# robot_vac.net
KiCad netlist of a schematic drawn in EAGLE
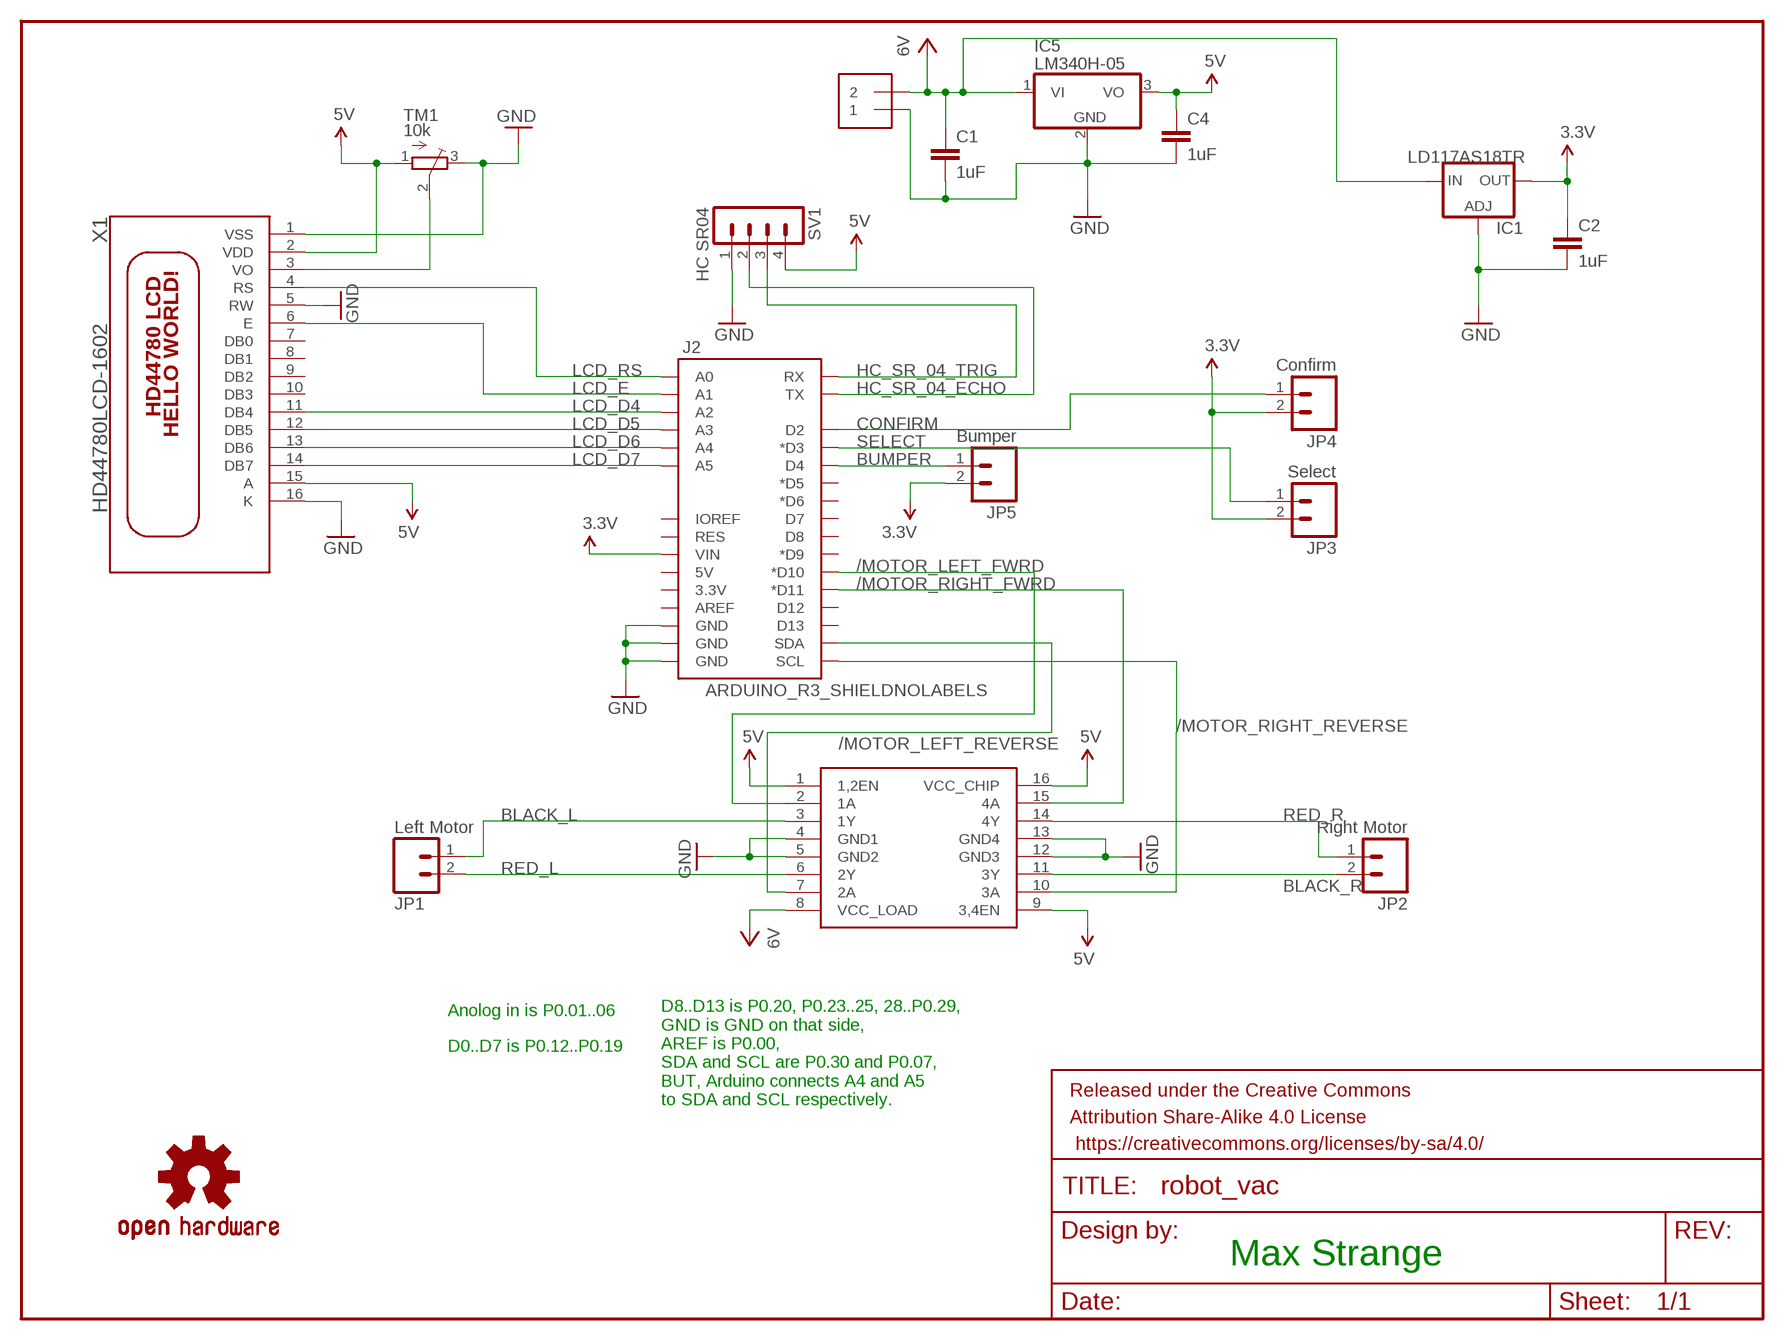
[diagram p0: schematic, sheet 1]

(export (version "E")
  (design (tool "Eeschema 10.0.6"))
  (components
    (comp (ref "C1")
      (value "1uF")
      (footprint "eagle-import:CAP-PTH-SMALL")
      (libsource (lib "eagle-import") (part "CAPPTH"))
    )
    (comp (ref "C2")
      (value "1uF")
      (footprint "eagle-import:CAP-PTH-SMALL")
      (libsource (lib "eagle-import") (part "CAPPTH"))
    )
    (comp (ref "C4")
      (value "1uF")
      (footprint "eagle-import:CAP-PTH-SMALL")
      (libsource (lib "eagle-import") (part "CAPPTH"))
    )
    (comp (ref "FRAME1")
      (value "FRAME-LETTERNO_PACKAGE")
      (footprint "eagle-import:DUMMY")
      (fields (field (name "DESIGNER") "Nobody"))
      (libsource (lib "eagle-import") (part "FRAME-LETTERNO_PACKAGE"))
    )
    (comp (ref "H_BRIDGE")
      (value "SN75441_H_BRIDGE")
      (footprint "eagle-import:DIL16")
      (libsource (lib "eagle-import") (part "SN75441_H_BRIDGE"))
    )
    (comp (ref "IC1")
      (value "LD117AS18TR")
      (footprint "eagle-import:SOT223")
      (libsource (lib "eagle-import") (part "LD117A?S18TR"))
    )
    (comp (ref "IC5")
      (value "LM340H-05")
      (footprint "eagle-import:TO220H")
      (libsource (lib "eagle-import") (part "LM340?-H05"))
    )
    (comp (ref "J1")
      (value "1X2-3.5MM")
      (footprint "eagle-import:1X2-3.5MM")
      (libsource (lib "eagle-import") (part "1X2-3.5MM"))
    )
    (comp (ref "J2")
      (value "ARDUINO_R3_SHIELDNOLABELS")
      (footprint "eagle-import:UNO_R3_SHIELD_NOLABELS")
      (libsource (lib "eagle-import") (part "ARDUINO_R3_SHIELDNOLABELS"))
    )
    (comp (ref "JP1")
      (value "Left Motor")
      (footprint "eagle-import:1X02_LOCK")
      (libsource (lib "eagle-import") (part "M02LOCK"))
    )
    (comp (ref "JP2")
      (value "Right Motor")
      (footprint "eagle-import:1X02_LOCK")
      (libsource (lib "eagle-import") (part "M02LOCK"))
    )
    (comp (ref "JP3")
      (value "Select")
      (footprint "eagle-import:1X02_LOCK")
      (libsource (lib "eagle-import") (part "M02LOCK"))
    )
    (comp (ref "JP4")
      (value "Confirm")
      (footprint "eagle-import:1X02_LOCK")
      (libsource (lib "eagle-import") (part "M02LOCK"))
    )
    (comp (ref "JP5")
      (value "Bumper")
      (footprint "eagle-import:1X02_LOCK")
      (libsource (lib "eagle-import") (part "M02LOCK"))
    )
    (comp (ref "LOGO1")
      (value "OSHW-LOGOL")
      (footprint "eagle-import:OSHW-LOGO-L")
      (libsource (lib "eagle-import") (part "OSHW-LOGOL"))
    )
    (comp (ref "SV1")
      (value "HC SR04")
      (footprint "eagle-import:MA04-1")
      (libsource (lib "eagle-import") (part "MA04-1"))
    )
    (comp (ref "TM1")
      (value "10k")
      (footprint "eagle-import:TRIM-3386")
      (libsource (lib "eagle-import") (part "TRIMPOT3386"))
    )
    (comp (ref "X1")
      (value "HD44780LCD-1602")
      (footprint "eagle-import:LCD1602")
      (libsource (lib "eagle-import") (part "HD44780LCD-1602"))
    )
  )
  (nets
    (net (code "1") (name "/BLACK_L") (class "Default")
      (node (ref "H_BRIDGE") (pin "3") (pinfunction "1Y_3") (pintype "bidirectional"))
      (node (ref "JP1") (pin "1") (pinfunction "1_1") (pintype "passive"))
    )
    (net (code "2") (name "/BLACK_R") (class "Default")
      (node (ref "H_BRIDGE") (pin "11") (pinfunction "3Y_11") (pintype "bidirectional"))
      (node (ref "JP2") (pin "2") (pinfunction "2_2") (pintype "passive"))
    )
    (net (code "3") (name "/BUMPER") (class "Default")
      (node (ref "J2") (pin "D4") (pinfunction "D4_D4") (pintype "bidirectional"))
      (node (ref "JP5") (pin "1") (pinfunction "1_1") (pintype "passive"))
    )
    (net (code "4") (name "/CONFIRM") (class "Default")
      (node (ref "J2") (pin "D2") (pinfunction "D2_D2") (pintype "bidirectional"))
      (node (ref "JP4") (pin "1") (pinfunction "1_1") (pintype "passive"))
    )
    (net (code "5") (name "/HC_SR_04_ECHO") (class "Default")
      (node (ref "J2") (pin "TX") (pinfunction "TX_TX") (pintype "bidirectional"))
      (node (ref "SV1") (pin "2") (pinfunction "2_2") (pintype "passive"))
    )
    (net (code "6") (name "/HC_SR_04_TRIG") (class "Default")
      (node (ref "J2") (pin "RX") (pinfunction "RX_RX") (pintype "bidirectional"))
      (node (ref "SV1") (pin "3") (pinfunction "3_3") (pintype "passive"))
    )
    (net (code "7") (name "/LCD_D4") (class "Default")
      (node (ref "J2") (pin "A2") (pinfunction "A2_A2") (pintype "bidirectional"))
      (node (ref "X1") (pin "11") (pinfunction "DB4_11") (pintype "bidirectional"))
    )
    (net (code "8") (name "/LCD_D5") (class "Default")
      (node (ref "J2") (pin "A3") (pinfunction "A3_A3") (pintype "bidirectional"))
      (node (ref "X1") (pin "12") (pinfunction "DB5_12") (pintype "bidirectional"))
    )
    (net (code "9") (name "/LCD_D6") (class "Default")
      (node (ref "J2") (pin "A4") (pinfunction "A4_A4") (pintype "bidirectional"))
      (node (ref "X1") (pin "13") (pinfunction "DB6_13") (pintype "bidirectional"))
    )
    (net (code "10") (name "/LCD_D7") (class "Default")
      (node (ref "J2") (pin "A5") (pinfunction "A5_A5") (pintype "bidirectional"))
      (node (ref "X1") (pin "14") (pinfunction "DB7_14") (pintype "bidirectional"))
    )
    (net (code "11") (name "/LCD_E") (class "Default")
      (node (ref "J2") (pin "A1") (pinfunction "A1_A1") (pintype "bidirectional"))
      (node (ref "X1") (pin "6") (pinfunction "E_6") (pintype "input"))
    )
    (net (code "12") (name "/LCD_RS") (class "Default")
      (node (ref "J2") (pin "A0") (pinfunction "A0_A0") (pintype "bidirectional"))
      (node (ref "X1") (pin "4") (pinfunction "RS_4") (pintype "input"))
    )
    (net (code "13") (name "/RED_L") (class "Default")
      (node (ref "H_BRIDGE") (pin "6") (pinfunction "2Y_6") (pintype "bidirectional"))
      (node (ref "JP1") (pin "2") (pinfunction "2_2") (pintype "passive"))
    )
    (net (code "14") (name "/RED_R") (class "Default")
      (node (ref "H_BRIDGE") (pin "14") (pinfunction "4Y_14") (pintype "bidirectional"))
      (node (ref "JP2") (pin "1") (pinfunction "1_1") (pintype "passive"))
    )
    (net (code "15") (name "/SELECT") (class "Default")
      (node (ref "J2") (pin "D3") (pinfunction "*D3_D3") (pintype "bidirectional"))
      (node (ref "JP3") (pin "1") (pinfunction "1_1") (pintype "passive"))
    )
    (net (code "16") (name "/{slash}MOTOR_LEFT_FWRD") (class "Default")
      (node (ref "H_BRIDGE") (pin "2") (pinfunction "1A_2") (pintype "bidirectional"))
      (node (ref "J2") (pin "D10") (pinfunction "*D10_D10") (pintype "bidirectional"))
    )
    (net (code "17") (name "/{slash}MOTOR_LEFT_REVERSE") (class "Default")
      (node (ref "H_BRIDGE") (pin "7") (pinfunction "2A_7") (pintype "bidirectional"))
      (node (ref "J2") (pin "SDA") (pinfunction "SDA_SDA") (pintype "bidirectional"))
    )
    (net (code "18") (name "/{slash}MOTOR_RIGHT_FWRD") (class "Default")
      (node (ref "H_BRIDGE") (pin "15") (pinfunction "4A_15") (pintype "bidirectional"))
      (node (ref "J2") (pin "D11") (pinfunction "*D11_D11") (pintype "bidirectional"))
    )
    (net (code "19") (name "/{slash}MOTOR_RIGHT_REVERSE") (class "Default")
      (node (ref "H_BRIDGE") (pin "10") (pinfunction "3A_10") (pintype "bidirectional"))
      (node (ref "J2") (pin "SCL") (pinfunction "SCL_SCL") (pintype "bidirectional"))
    )
    (net (code "20") (name "3.3V") (class "Default")
      (node (ref "C2") (pin "1") (pinfunction "1_1") (pintype "passive"))
      (node (ref "IC1") (pin "4") (pinfunction "OUT_4") (pintype "passive"))
      (node (ref "J2") (pin "VIN") (pinfunction "VIN_VIN") (pintype "bidirectional"))
      (node (ref "JP3") (pin "2") (pinfunction "2_2") (pintype "passive"))
      (node (ref "JP4") (pin "2") (pinfunction "2_2") (pintype "passive"))
      (node (ref "JP5") (pin "2") (pinfunction "2_2") (pintype "passive"))
    )
    (net (code "21") (name "5V") (class "Default")
      (node (ref "C4") (pin "1") (pinfunction "1_1") (pintype "passive"))
      (node (ref "H_BRIDGE") (pin "1") (pinfunction "1,2EN_1") (pintype "bidirectional"))
      (node (ref "H_BRIDGE") (pin "16") (pinfunction "VCC_CHIP_16") (pintype "bidirectional"))
      (node (ref "H_BRIDGE") (pin "9") (pinfunction "3,4EN_9") (pintype "bidirectional"))
      (node (ref "IC5") (pin "3") (pinfunction "VO_3") (pintype "passive"))
      (node (ref "SV1") (pin "4") (pinfunction "4_4") (pintype "passive"))
      (node (ref "TM1") (pin "1") (pinfunction "A_1") (pintype "passive"))
      (node (ref "X1") (pin "15") (pinfunction "A_15") (pintype "input"))
      (node (ref "X1") (pin "2") (pinfunction "VDD_2") (pintype "power_in"))
    )
    (net (code "22") (name "6V") (class "Default")
      (node (ref "C1") (pin "1") (pinfunction "1_1") (pintype "passive"))
      (node (ref "H_BRIDGE") (pin "8") (pinfunction "VCC_LOAD_8") (pintype "bidirectional"))
      (node (ref "IC1") (pin "3") (pinfunction "IN_3") (pintype "input"))
      (node (ref "IC5") (pin "1") (pinfunction "VI_1") (pintype "input"))
      (node (ref "J1") (pin "2") (pinfunction "2_2") (pintype "passive"))
    )
    (net (code "23") (name "GND") (class "Default")
      (node (ref "C1") (pin "2") (pinfunction "2_2") (pintype "passive"))
      (node (ref "C2") (pin "2") (pinfunction "2_2") (pintype "passive"))
      (node (ref "C4") (pin "2") (pinfunction "2_2") (pintype "passive"))
      (node (ref "H_BRIDGE") (pin "12") (pinfunction "GND3_12") (pintype "bidirectional"))
      (node (ref "H_BRIDGE") (pin "13") (pinfunction "GND4_13") (pintype "bidirectional"))
      (node (ref "H_BRIDGE") (pin "4") (pinfunction "GND1_4") (pintype "bidirectional"))
      (node (ref "H_BRIDGE") (pin "5") (pinfunction "GND2_5") (pintype "bidirectional"))
      (node (ref "IC1") (pin "1") (pinfunction "ADJ_1") (pintype "input"))
      (node (ref "IC5") (pin "2") (pinfunction "GND_2") (pintype "passive"))
      (node (ref "J1") (pin "1") (pinfunction "1_1") (pintype "passive"))
      (node (ref "J2") (pin "GND@0") (pinfunction "GND_GND@0") (pintype "bidirectional"))
      (node (ref "J2") (pin "GND@1") (pinfunction "GND_GND@1") (pintype "bidirectional"))
      (node (ref "J2") (pin "GND@2") (pinfunction "GND_GND@2") (pintype "bidirectional"))
      (node (ref "SV1") (pin "1") (pinfunction "1_1") (pintype "passive"))
      (node (ref "TM1") (pin "3") (pinfunction "E_3") (pintype "passive"))
      (node (ref "X1") (pin "1") (pinfunction "VSS_1") (pintype "power_in"))
      (node (ref "X1") (pin "16") (pinfunction "K_16") (pintype "input"))
      (node (ref "X1") (pin "5") (pinfunction "RW_5") (pintype "input"))
    )
    (net (code "24") (name "Net-(TM1-S)") (class "Default")
      (node (ref "TM1") (pin "2") (pinfunction "S_2") (pintype "passive"))
      (node (ref "X1") (pin "3") (pinfunction "VO_3") (pintype "input"))
    )
    (net (code "25") (name "unconnected-(J2-*D5-PadD5)") (class "Default")
      (node (ref "J2") (pin "D5") (pinfunction "*D5_D5") (pintype "bidirectional"))
    )
    (net (code "26") (name "unconnected-(J2-*D6-PadD6)") (class "Default")
      (node (ref "J2") (pin "D6") (pinfunction "*D6_D6") (pintype "bidirectional"))
    )
    (net (code "27") (name "unconnected-(J2-*D9-PadD9)") (class "Default")
      (node (ref "J2") (pin "D9") (pinfunction "*D9_D9") (pintype "bidirectional"))
    )
    (net (code "28") (name "unconnected-(J2-Pad3.3V)") (class "Default")
      (node (ref "J2") (pin "3.3V") (pinfunction "3.3V_3.3V") (pintype "bidirectional"))
    )
    (net (code "29") (name "unconnected-(J2-Pad5V)") (class "Default")
      (node (ref "J2") (pin "5V") (pinfunction "5V_5V") (pintype "bidirectional"))
    )
    (net (code "30") (name "unconnected-(J2-PadAREF)") (class "Default")
      (node (ref "J2") (pin "AREF") (pinfunction "AREF_AREF") (pintype "bidirectional"))
    )
    (net (code "31") (name "unconnected-(J2-PadD7)") (class "Default")
      (node (ref "J2") (pin "D7") (pinfunction "D7_D7") (pintype "bidirectional"))
    )
    (net (code "32") (name "unconnected-(J2-PadD8)") (class "Default")
      (node (ref "J2") (pin "D8") (pinfunction "D8_D8") (pintype "bidirectional"))
    )
    (net (code "33") (name "unconnected-(J2-PadD12)") (class "Default")
      (node (ref "J2") (pin "D12") (pinfunction "D12_D12") (pintype "bidirectional"))
    )
    (net (code "34") (name "unconnected-(J2-PadD13)") (class "Default")
      (node (ref "J2") (pin "D13") (pinfunction "D13_D13") (pintype "bidirectional"))
    )
    (net (code "35") (name "unconnected-(J2-PadIOREF)") (class "Default")
      (node (ref "J2") (pin "IOREF") (pinfunction "IOREF_IOREF") (pintype "bidirectional"))
    )
    (net (code "36") (name "unconnected-(J2-PadRES)") (class "Default")
      (node (ref "J2") (pin "RES") (pinfunction "RES_RES") (pintype "bidirectional"))
    )
    (net (code "37") (name "unconnected-(X1-DB0-Pad7)") (class "Default")
      (node (ref "X1") (pin "7") (pinfunction "DB0_7") (pintype "bidirectional"))
    )
    (net (code "38") (name "unconnected-(X1-DB1-Pad8)") (class "Default")
      (node (ref "X1") (pin "8") (pinfunction "DB1_8") (pintype "bidirectional"))
    )
    (net (code "39") (name "unconnected-(X1-DB2-Pad9)") (class "Default")
      (node (ref "X1") (pin "9") (pinfunction "DB2_9") (pintype "bidirectional"))
    )
    (net (code "40") (name "unconnected-(X1-DB3-Pad10)") (class "Default")
      (node (ref "X1") (pin "10") (pinfunction "DB3_10") (pintype "bidirectional"))
    )
  )
)
